# CH32V005D6U6.net
KiCad netlist of a schematic drawn in Altium Designer
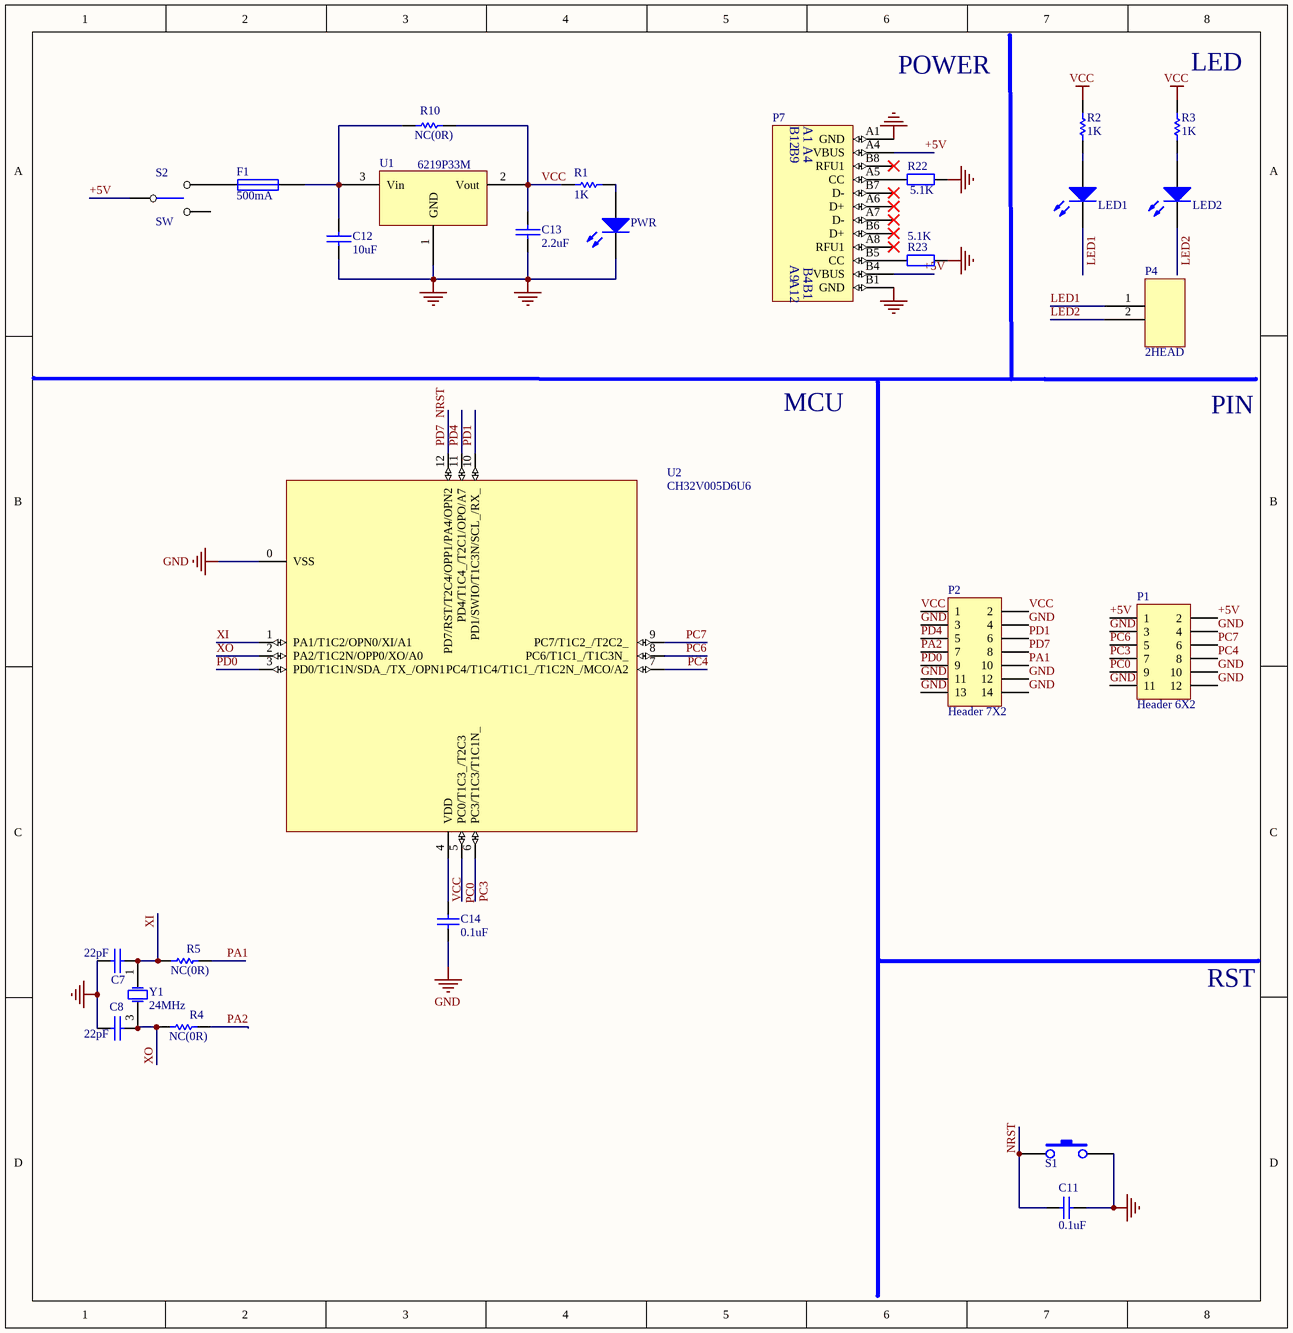
[diagram p0: CH32V005D6U6.SchDoc]

(export (version "E")
  (design (tool "Eeschema 10.0.6"))
  (components
    (comp (ref "C7")
      (value "22pF")
      (footprint "0402_C")
      (description "Capacitor")
      (libsource (lib "*") (part "CAP"))
    )
    (comp (ref "C8")
      (value "22pF")
      (footprint "0402_C")
      (description "Capacitor")
      (libsource (lib "*") (part "CAP"))
    )
    (comp (ref "C11")
      (value "0.1uF")
      (footprint "0603_C")
      (description "Capacitor")
      (fields (field (name "PUBLISHER") "Altium Limited"))
      (libsource (lib "*") (part "Cap"))
    )
    (comp (ref "C12")
      (value "10uF")
      (footprint "0603_C")
      (description "Capacitor")
      (libsource (lib "wch_sch_others") (part "CAP"))
    )
    (comp (ref "C13")
      (value "2.2uF")
      (footprint "0402_C")
      (description "Capacitor")
      (libsource (lib "wch_sch_others") (part "CAP"))
    )
    (comp (ref "C14")
      (value "0.1uF")
      (footprint "0603_C")
      (description "Capacitor")
      (fields (field (name "PUBLISHER") "Altium Limited"))
      (libsource (lib "*") (part "Cap"))
    )
    (comp (ref "F1")
      (value "500mA")
      (footprint "0603")
      (description "Fuse")
      (libsource (lib "*") (part "FUSE1"))
    )
    (comp (ref "LED1")
      (value "LED1   blue")
      (footprint "0603+")
      (description "Typical INFRARED GaAs LED")
      (fields (field (name "PUBLISHER") "Altium Limited"))
      (libsource (lib "") (part "LED0_1"))
    )
    (comp (ref "LED2")
      (value "LED2  blue")
      (footprint "0603+")
      (description "Typical INFRARED GaAs LED")
      (fields (field (name "PUBLISHER") "Altium Limited"))
      (libsource (lib "") (part "LED0_1"))
    )
    (comp (ref "P1")
      (value "Header 6X2")
      (footprint "HDR2X6")
      (description "Header, 6-Pin, Dual row")
      (fields (field (name "PUBLISHER") "Altium Limited"))
      (libsource (lib "Miscellaneous Connectors") (part "Header 6X2"))
    )
    (comp (ref "P2")
      (value "Header 7X2")
      (footprint "HDR2X7")
      (description "Header, 7-Pin, Dual row")
      (fields (field (name "PUBLISHER") "Altium Limited"))
      (libsource (lib "Miscellaneous Connectors") (part "Header 7X2"))
    )
    (comp (ref "P4") (value "2HEAD") (footprint "SIP2-2.54mm") (libsource (lib "*") (part "2HEAD")))
    (comp (ref "P7")
      (value "TYPE-C")
      (footprint "TYPE-C-Receptacle-2.0")
      (libsource (lib "*") (part "TYPE-C1"))
    )
    (comp (ref "PWR")
      (value "POWER  red")
      (footprint "0603+")
      (description "Typical INFRARED GaAs LED")
      (fields (field (name "PUBLISHER") "Altium Limited"))
      (libsource (lib "*") (part "LED0"))
    )
    (comp (ref "R1")
      (value "1K")
      (footprint "0402")
      (description "Semiconductor Resistor")
      (fields (field (name "PUBLISHER") "Altium Limited"))
      (libsource (lib "*") (part "Res Semi"))
    )
    (comp (ref "R2")
      (value "1K")
      (footprint "0402")
      (description "Semiconductor Resistor")
      (fields (field (name "PUBLISHER") "Altium Limited"))
      (libsource (lib "*") (part "Res Semi"))
    )
    (comp (ref "R3")
      (value "1K")
      (footprint "0402")
      (description "Semiconductor Resistor")
      (fields (field (name "PUBLISHER") "Altium Limited"))
      (libsource (lib "*") (part "Res Semi"))
    )
    (comp (ref "R4")
      (value "NC(0R)")
      (footprint "0402")
      (description "Semiconductor Resistor")
      (fields (field (name "Comment") "0R") (field (name "PUBLISHER") "Altium Limited"))
      (libsource (lib "*") (part "Res Semi"))
    )
    (comp (ref "R5")
      (value "NC(0R)")
      (footprint "0402")
      (description "Semiconductor Resistor")
      (fields (field (name "Comment") "0R") (field (name "PUBLISHER") "Altium Limited"))
      (libsource (lib "*") (part "Res Semi"))
    )
    (comp (ref "R10")
      (value "NC(0R)")
      (footprint "0402")
      (description "Semiconductor Resistor")
      (fields (field (name "Comment") "0R") (field (name "PUBLISHER") "Altium Limited"))
      (libsource (lib "*") (part "Res Semi"))
    )
    (comp (ref "R22")
      (value "5.1K")
      (footprint "0402")
      (description "Resistor")
      (libsource (lib "Miscellaneous Devices") (part "Res2"))
    )
    (comp (ref "R23")
      (value "5.1K")
      (footprint "0402")
      (description "Resistor")
      (libsource (lib "Miscellaneous Devices") (part "Res2"))
    )
    (comp (ref "S1") (value "NRST") (footprint "SMD_6.1x3.65x2.5mm-KEY") (libsource (lib "*") (part "KEY")))
    (comp (ref "S2") (value "SW") (footprint "SW1") (libsource (lib "*") (part "SW")))
    (comp (ref "U1")
      (value "6219P33M")
      (footprint "SOT-23")
      (libsource (lib "wch_sch_others") (part "6219P33M"))
    )
    (comp (ref "U2")
      (value "CH32V005D6U6")
      (footprint "QFN12_2X2")
      (description "RISC-V MCU, 48MHz, ADC/OPA/2*UART/I2C")
      (libsource (lib "DHXXXSCH") (part "CH32V005D6U6"))
    )
    (comp (ref "Y1")
      (value "24MHz")
      (footprint "XT3225")
      (description "Crystal Oscillator")
      (fields (field (name "PUBLISHER") "Altium Limited"))
      (libsource (lib "*") (part "XTAL"))
    )
  )
  (nets
    (net (code "1") (name "/+5V") (class "Default")
      (node (ref "P1") (pin "1") (pinfunction "1_1") (pintype "passive"))
      (node (ref "P1") (pin "2") (pinfunction "2_2") (pintype "passive"))
      (node (ref "P7") (pin "A4") (pinfunction "VBUS_A4") (pintype "bidirectional"))
      (node (ref "P7") (pin "B4") (pinfunction "VBUS_B4") (pintype "bidirectional"))
      (node (ref "S2") (pin "1") (pinfunction "1_1") (pintype "passive"))
    )
    (net (code "2") (name "/LED1") (class "Default")
      (node (ref "LED1") (pin "2") (pinfunction "K_2") (pintype "passive"))
      (node (ref "P4") (pin "1") (pintype "passive"))
    )
    (net (code "3") (name "/LED2") (class "Default")
      (node (ref "LED2") (pin "2") (pinfunction "K_2") (pintype "passive"))
      (node (ref "P4") (pin "2") (pintype "passive"))
    )
    (net (code "4") (name "/NRST") (class "Default")
      (node (ref "C11") (pin "2") (pinfunction "2_2") (pintype "passive"))
      (node (ref "P2") (pin "8") (pinfunction "8_8") (pintype "passive"))
      (node (ref "S1") (pin "1") (pinfunction "1_1") (pintype "passive"))
      (node (ref "U2") (pin "12") (pinfunction "PD7/RST/T2C4/OPP1/PA4/OPN2_12") (pintype "bidirectional"))
    )
    (net (code "5") (name "/PA1") (class "Default")
      (node (ref "P2") (pin "10") (pinfunction "10_10") (pintype "passive"))
      (node (ref "R5") (pin "2") (pinfunction "2_2") (pintype "passive"))
    )
    (net (code "6") (name "/PA2") (class "Default")
      (node (ref "P2") (pin "7") (pinfunction "7_7") (pintype "passive"))
      (node (ref "R4") (pin "2") (pinfunction "2_2") (pintype "passive"))
    )
    (net (code "7") (name "/PC0") (class "Default")
      (node (ref "P1") (pin "9") (pinfunction "9_9") (pintype "passive"))
      (node (ref "U2") (pin "5") (pinfunction "PC0/T1C3_/T2C3_5") (pintype "bidirectional"))
    )
    (net (code "8") (name "/PC3") (class "Default")
      (node (ref "P1") (pin "7") (pinfunction "7_7") (pintype "passive"))
      (node (ref "U2") (pin "6") (pinfunction "PC3/T1C3/T1C1N__6") (pintype "bidirectional"))
    )
    (net (code "9") (name "/PC4") (class "Default")
      (node (ref "P1") (pin "8") (pinfunction "8_8") (pintype "passive"))
      (node (ref "U2") (pin "7") (pinfunction "PC4/T1C4/T1C1_/T1C2N_/MCO/A2_7") (pintype "bidirectional"))
    )
    (net (code "10") (name "/PC6") (class "Default")
      (node (ref "P1") (pin "5") (pinfunction "5_5") (pintype "passive"))
      (node (ref "U2") (pin "8") (pinfunction "PC6/T1C1_/T1C3N__8") (pintype "bidirectional"))
    )
    (net (code "11") (name "/PC7") (class "Default")
      (node (ref "P1") (pin "6") (pinfunction "6_6") (pintype "passive"))
      (node (ref "U2") (pin "9") (pinfunction "PC7/T1C2_/T2C2__9") (pintype "bidirectional"))
    )
    (net (code "12") (name "/PD0") (class "Default")
      (node (ref "P2") (pin "9") (pinfunction "9_9") (pintype "passive"))
      (node (ref "U2") (pin "3") (pinfunction "PD0/T1C1N/SDA_/TX_/OPN1_3") (pintype "bidirectional"))
    )
    (net (code "13") (name "/PD1") (class "Default")
      (node (ref "P2") (pin "6") (pinfunction "6_6") (pintype "passive"))
      (node (ref "U2") (pin "10") (pinfunction "PD1/SWIO/T1C3N/SCL_/RX__10") (pintype "bidirectional"))
    )
    (net (code "14") (name "/PD4") (class "Default")
      (node (ref "P2") (pin "5") (pinfunction "5_5") (pintype "passive"))
      (node (ref "U2") (pin "11") (pinfunction "PD4/T1C4_/T2C1/OPO/A7_11") (pintype "bidirectional"))
    )
    (net (code "15") (name "/XI") (class "Default")
      (node (ref "C7") (pin "2") (pinfunction "2_2") (pintype "passive"))
      (node (ref "R5") (pin "1") (pinfunction "1_1") (pintype "passive"))
      (node (ref "U2") (pin "1") (pinfunction "PA1/T1C2/OPN0/XI/A1_1") (pintype "bidirectional"))
      (node (ref "Y1") (pin "1") (pinfunction "OSC1_1") (pintype "passive"))
    )
    (net (code "16") (name "/XO") (class "Default")
      (node (ref "C8") (pin "2") (pinfunction "2_2") (pintype "passive"))
      (node (ref "R4") (pin "1") (pinfunction "1_1") (pintype "passive"))
      (node (ref "U2") (pin "2") (pinfunction "PA2/T1C2N/OPP0/XO/A0_2") (pintype "bidirectional"))
      (node (ref "Y1") (pin "3") (pinfunction "OSC2_3") (pintype "passive"))
    )
    (net (code "17") (name "GND") (class "Default")
      (node (ref "C11") (pin "1") (pinfunction "1_1") (pintype "passive"))
      (node (ref "C12") (pin "2") (pinfunction "2_2") (pintype "passive"))
      (node (ref "C13") (pin "1") (pinfunction "1_1") (pintype "passive"))
      (node (ref "C14") (pin "1") (pinfunction "1_1") (pintype "passive"))
      (node (ref "C7") (pin "1") (pinfunction "1_1") (pintype "passive"))
      (node (ref "C8") (pin "1") (pinfunction "1_1") (pintype "passive"))
      (node (ref "P1") (pin "10") (pinfunction "10_10") (pintype "passive"))
      (node (ref "P1") (pin "11") (pinfunction "11_11") (pintype "passive"))
      (node (ref "P1") (pin "12") (pinfunction "12_12") (pintype "passive"))
      (node (ref "P1") (pin "3") (pinfunction "3_3") (pintype "passive"))
      (node (ref "P1") (pin "4") (pinfunction "4_4") (pintype "passive"))
      (node (ref "P2") (pin "11") (pinfunction "11_11") (pintype "passive"))
      (node (ref "P2") (pin "12") (pinfunction "12_12") (pintype "passive"))
      (node (ref "P2") (pin "13") (pinfunction "13_13") (pintype "passive"))
      (node (ref "P2") (pin "14") (pinfunction "14_14") (pintype "passive"))
      (node (ref "P2") (pin "3") (pinfunction "3_3") (pintype "passive"))
      (node (ref "P2") (pin "4") (pinfunction "4_4") (pintype "passive"))
      (node (ref "P7") (pin "A1") (pinfunction "GND_A1") (pintype "bidirectional"))
      (node (ref "P7") (pin "B1") (pinfunction "GND_B1") (pintype "bidirectional"))
      (node (ref "PWR") (pin "2") (pinfunction "K_2") (pintype "passive"))
      (node (ref "R22") (pin "2") (pinfunction "2_2") (pintype "passive"))
      (node (ref "R23") (pin "2") (pinfunction "2_2") (pintype "passive"))
      (node (ref "S1") (pin "2") (pinfunction "2_2") (pintype "passive"))
      (node (ref "U1") (pin "1") (pinfunction "GND_1") (pintype "passive"))
      (node (ref "U2") (pin "0") (pinfunction "VSS_0") (pintype "power_in"))
    )
    (net (code "18") (name "Net-(F1-Pad1)") (class "Default")
      (node (ref "F1") (pin "1") (pinfunction "1_1") (pintype "passive"))
      (node (ref "S2") (pin "3") (pinfunction "3_3") (pintype "passive"))
    )
    (net (code "19") (name "Net-(LED1-A)") (class "Default")
      (node (ref "LED1") (pin "1") (pinfunction "A_1") (pintype "passive"))
      (node (ref "R2") (pin "2") (pinfunction "2_2") (pintype "passive"))
    )
    (net (code "20") (name "Net-(LED2-A)") (class "Default")
      (node (ref "LED2") (pin "1") (pinfunction "A_1") (pintype "passive"))
      (node (ref "R3") (pin "2") (pinfunction "2_2") (pintype "passive"))
    )
    (net (code "21") (name "Net-(P7-CC-PadA5)") (class "Default")
      (node (ref "P7") (pin "A5") (pinfunction "CC_A5") (pintype "bidirectional"))
      (node (ref "R22") (pin "1") (pinfunction "1_1") (pintype "passive"))
    )
    (net (code "22") (name "Net-(P7-CC-PadB5)") (class "Default")
      (node (ref "P7") (pin "B5") (pinfunction "CC_B5") (pintype "bidirectional"))
      (node (ref "R23") (pin "1") (pinfunction "1_1") (pintype "passive"))
    )
    (net (code "23") (name "Net-(PWR-A)") (class "Default")
      (node (ref "PWR") (pin "1") (pinfunction "A_1") (pintype "passive"))
      (node (ref "R1") (pin "1") (pinfunction "1_1") (pintype "passive"))
    )
    (net (code "24") (name "Net-(U1-Vin)") (class "Default")
      (node (ref "C12") (pin "1") (pinfunction "1_1") (pintype "passive"))
      (node (ref "F1") (pin "2") (pinfunction "2_2") (pintype "passive"))
      (node (ref "R10") (pin "1") (pinfunction "1_1") (pintype "passive"))
      (node (ref "U1") (pin "3") (pinfunction "Vin_3") (pintype "passive"))
    )
    (net (code "25") (name "VCC") (class "Default")
      (node (ref "C13") (pin "2") (pinfunction "2_2") (pintype "passive"))
      (node (ref "C14") (pin "2") (pinfunction "2_2") (pintype "passive"))
      (node (ref "P2") (pin "1") (pinfunction "1_1") (pintype "passive"))
      (node (ref "P2") (pin "2") (pinfunction "2_2") (pintype "passive"))
      (node (ref "R1") (pin "2") (pinfunction "2_2") (pintype "passive"))
      (node (ref "R10") (pin "2") (pinfunction "2_2") (pintype "passive"))
      (node (ref "R2") (pin "1") (pinfunction "1_1") (pintype "passive"))
      (node (ref "R3") (pin "1") (pinfunction "1_1") (pintype "passive"))
      (node (ref "U1") (pin "2") (pinfunction "Vout_2") (pintype "passive"))
      (node (ref "U2") (pin "4") (pinfunction "VDD_4") (pintype "power_in"))
    )
    (net (code "26") (name "unconnected-(P7-D+-PadA6)") (class "Default")
      (node (ref "P7") (pin "A6") (pinfunction "D+_A6") (pintype "bidirectional+no_connect"))
    )
    (net (code "27") (name "unconnected-(P7-D+-PadB6)") (class "Default")
      (node (ref "P7") (pin "B6") (pinfunction "D+_B6") (pintype "bidirectional+no_connect"))
    )
    (net (code "28") (name "unconnected-(P7-D--PadA7)") (class "Default")
      (node (ref "P7") (pin "A7") (pinfunction "D-_A7") (pintype "bidirectional+no_connect"))
    )
    (net (code "29") (name "unconnected-(P7-D--PadB7)") (class "Default")
      (node (ref "P7") (pin "B7") (pinfunction "D-_B7") (pintype "bidirectional+no_connect"))
    )
    (net (code "30") (name "unconnected-(P7-RFU1-PadA8)") (class "Default")
      (node (ref "P7") (pin "A8") (pinfunction "RFU1_A8") (pintype "bidirectional+no_connect"))
    )
    (net (code "31") (name "unconnected-(P7-RFU1-PadB8)") (class "Default")
      (node (ref "P7") (pin "B8") (pinfunction "RFU1_B8") (pintype "bidirectional+no_connect"))
    )
    (net (code "32") (name "unconnected-(S2-Pad2)") (class "Default")
      (node (ref "S2") (pin "2") (pinfunction "2_2") (pintype "passive"))
    )
  )
)
